# cooked-tomato.net
KiCad netlist of a schematic drawn in EAGLE
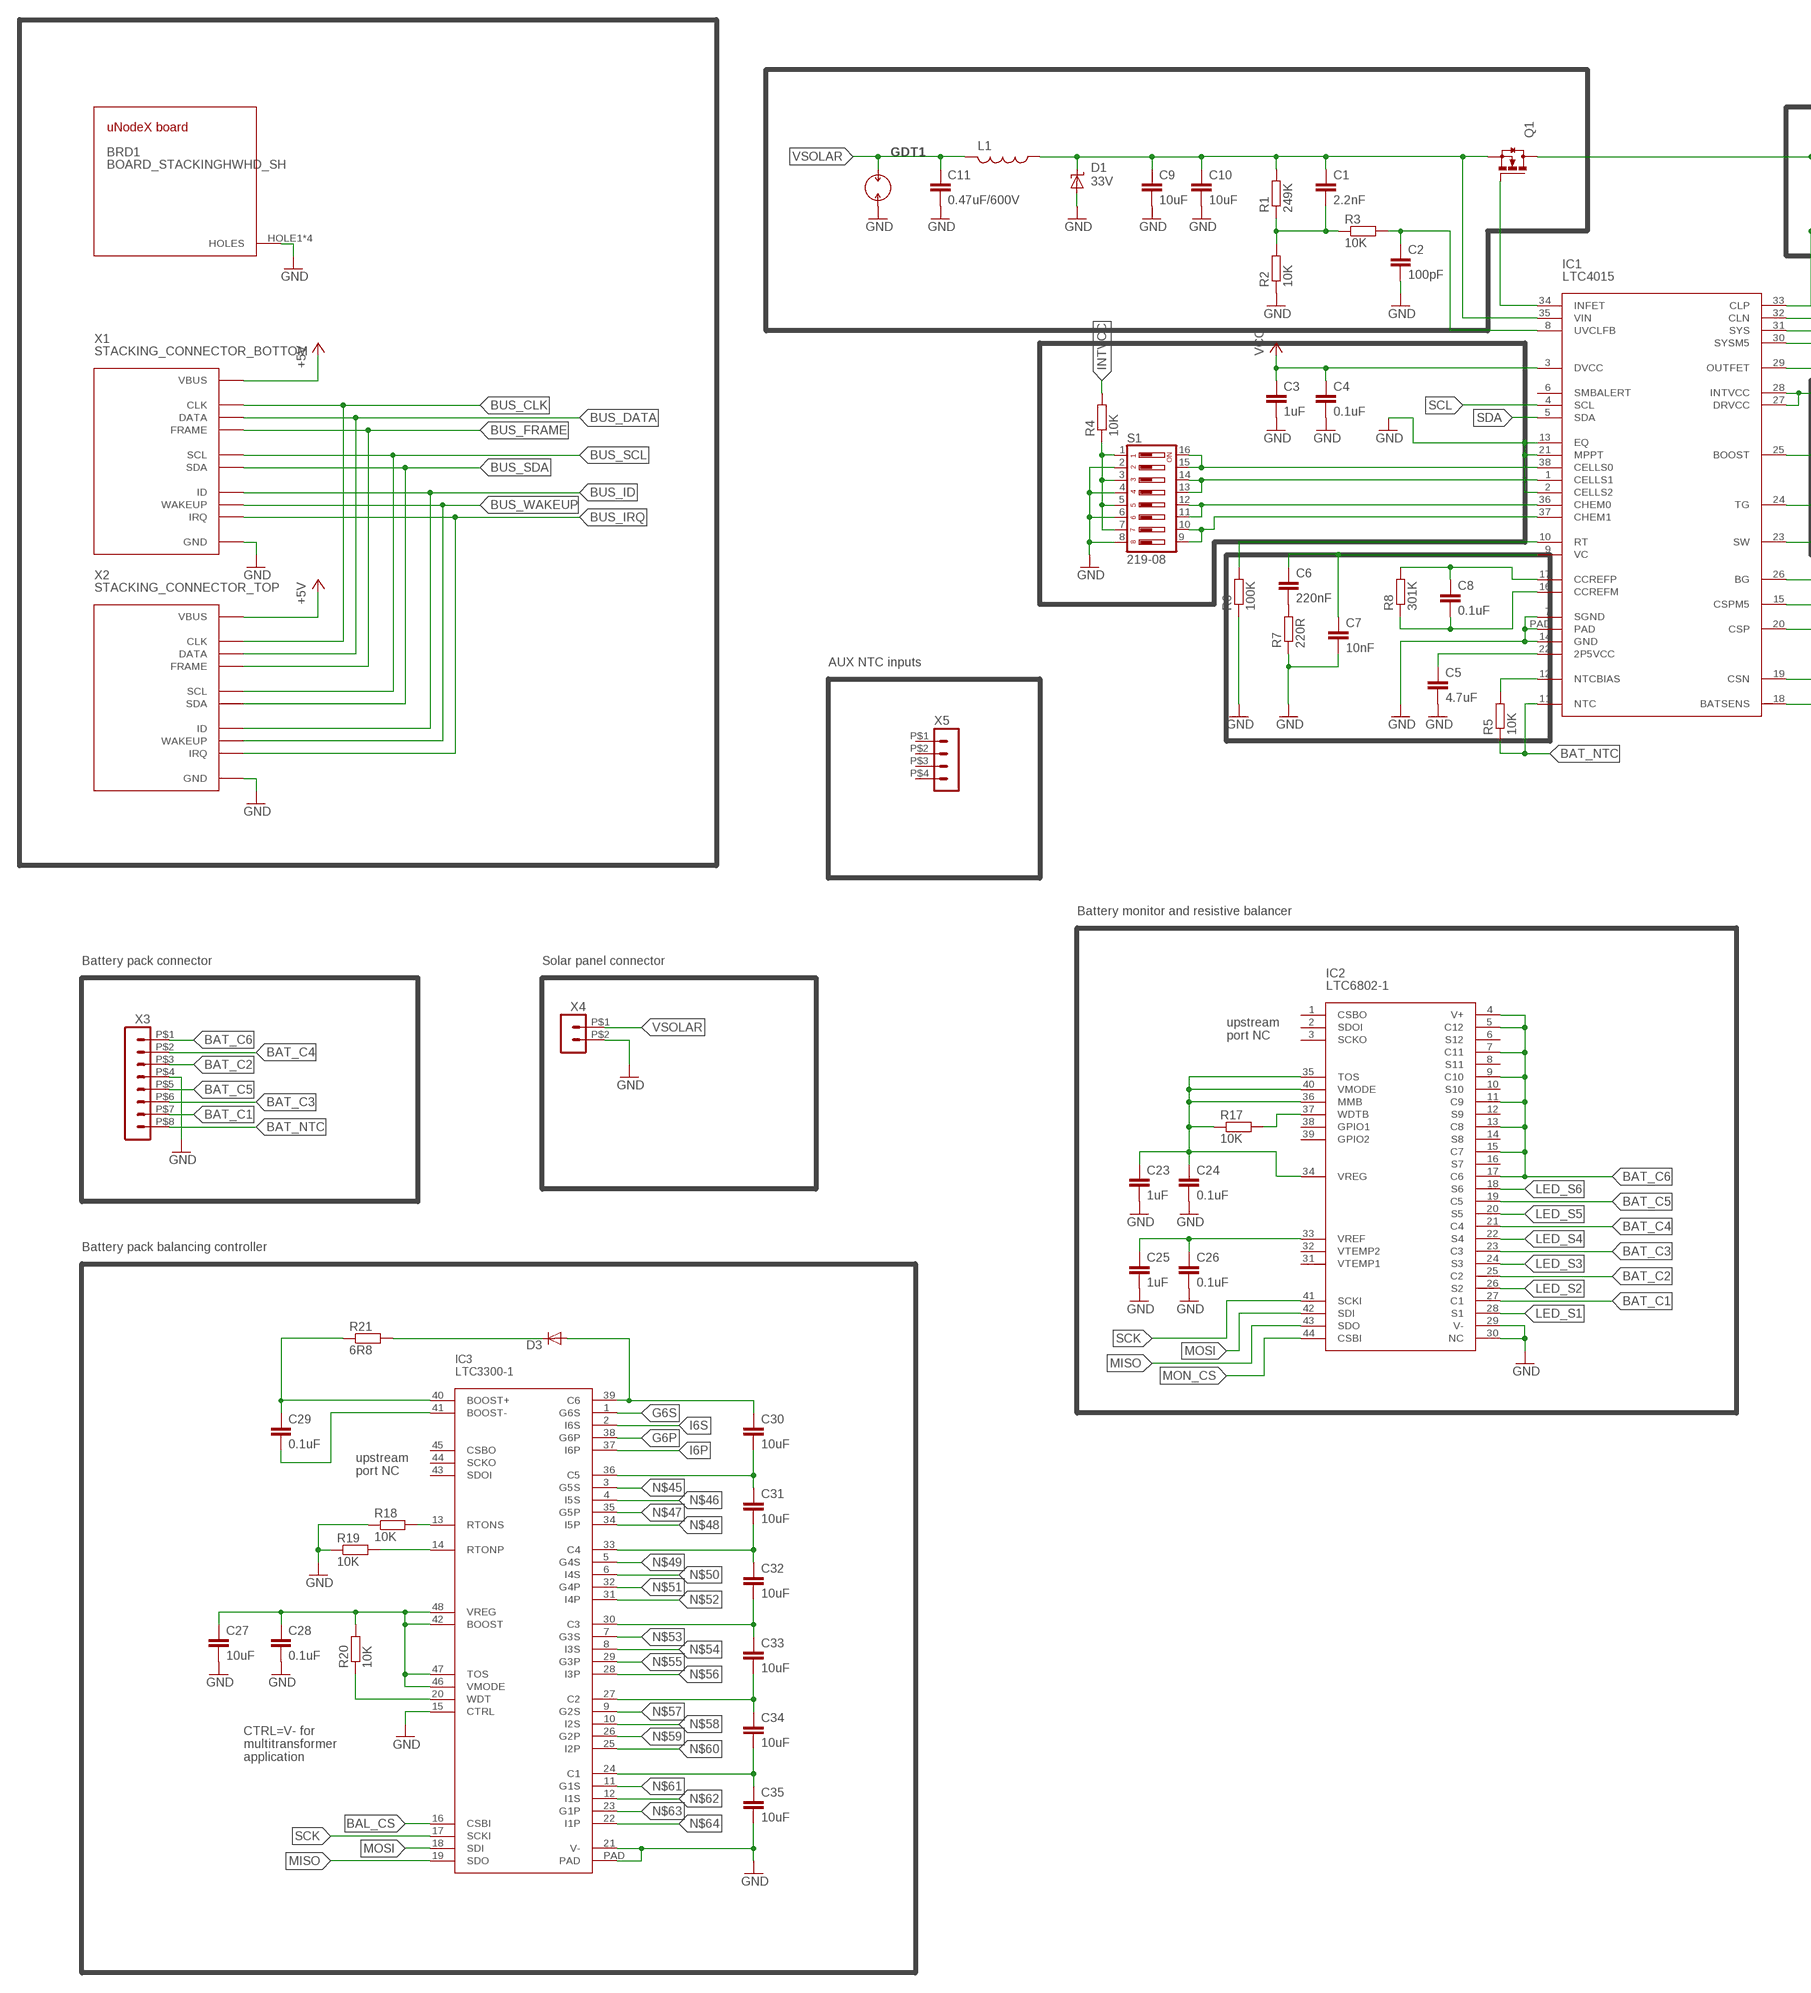
[diagram p0: schematic, sheet 1, part 1 of 3]
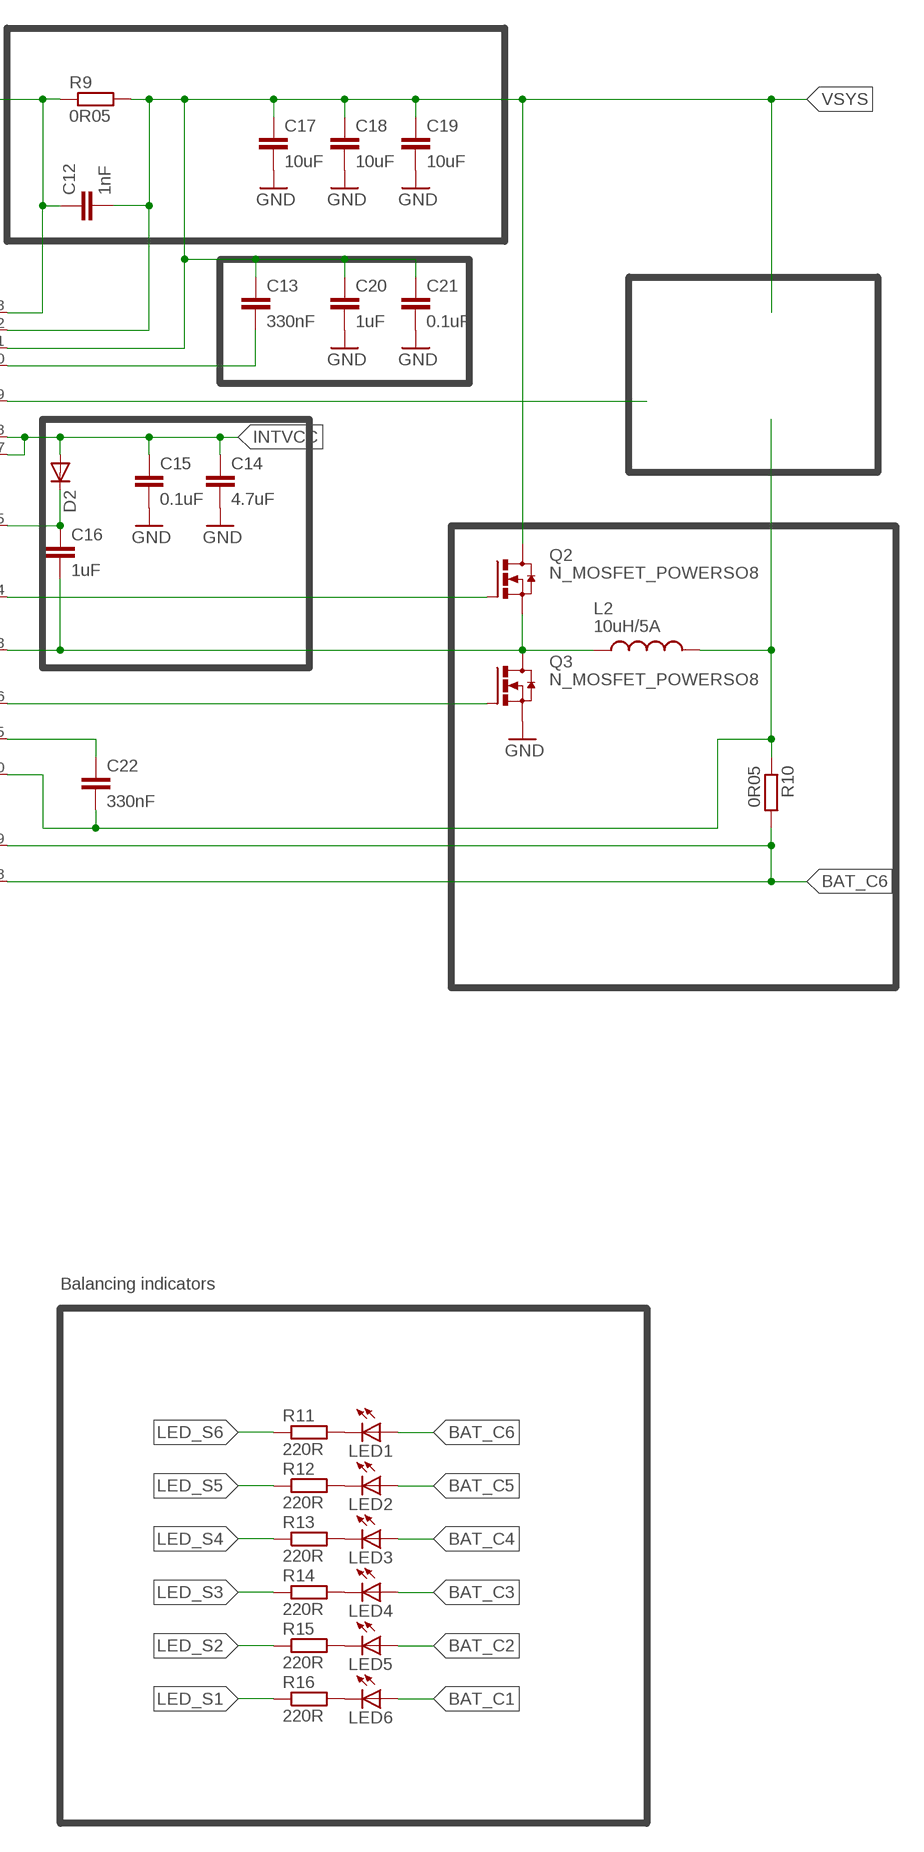
[diagram p1: schematic, sheet 1, part 2 of 3]
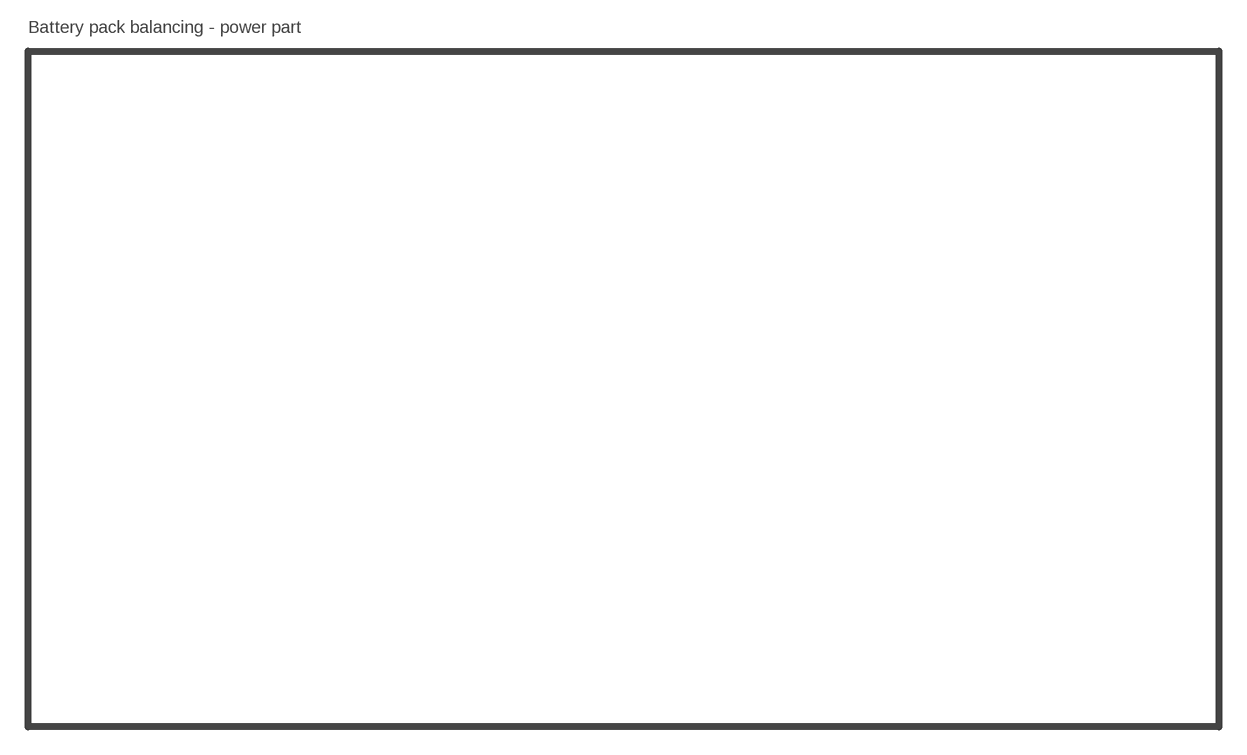
[diagram p2: schematic, sheet 1, part 3 of 3]

(export (version "E")
  (design (tool "Eeschema 10.0.6"))
  (components
    (comp (ref "BRD1")
      (value "BOARD_STACKINGHWHD_SH")
      (footprint "eagle-import:HWHD_SHARP_CORNERS")
      (libsource (lib "eagle-import") (part "BOARD_STACKINGHWHD_SH"))
    )
    (comp (ref "C1")
      (value "2.2nF")
      (footprint "eagle-import:C0603")
      (libsource (lib "eagle-import") (part "C-EUC0603"))
    )
    (comp (ref "C2")
      (value "100pF")
      (footprint "eagle-import:C0603")
      (libsource (lib "eagle-import") (part "C-EUC0603"))
    )
    (comp (ref "C3")
      (value "1uF")
      (footprint "eagle-import:C0603")
      (libsource (lib "eagle-import") (part "C-EUC0603"))
    )
    (comp (ref "C4")
      (value "0.1uF")
      (footprint "eagle-import:C0603")
      (libsource (lib "eagle-import") (part "C-EUC0603"))
    )
    (comp (ref "C5")
      (value "4.7uF")
      (footprint "eagle-import:C0805")
      (libsource (lib "eagle-import") (part "C-EUC0805"))
    )
    (comp (ref "C6")
      (value "220nF")
      (footprint "eagle-import:C0603")
      (libsource (lib "eagle-import") (part "C-EUC0603"))
    )
    (comp (ref "C7")
      (value "10nF")
      (footprint "eagle-import:C0603")
      (libsource (lib "eagle-import") (part "C-EUC0603"))
    )
    (comp (ref "C8")
      (value "0.1uF")
      (footprint "eagle-import:C0603")
      (libsource (lib "eagle-import") (part "C-EUC0603"))
    )
    (comp (ref "C9")
      (value "10uF")
      (footprint "eagle-import:C2220K")
      (libsource (lib "eagle-import") (part "C-EUC2220K"))
    )
    (comp (ref "C10")
      (value "10uF")
      (footprint "eagle-import:C2220K")
      (libsource (lib "eagle-import") (part "C-EUC2220K"))
    )
    (comp (ref "C11")
      (value "0.47uF/600V")
      (footprint "eagle-import:C1206")
      (libsource (lib "eagle-import") (part "C-EUC1206"))
    )
    (comp (ref "C12")
      (value "1nF")
      (footprint "eagle-import:C0603")
      (libsource (lib "eagle-import") (part "C-EUC0603"))
    )
    (comp (ref "C13")
      (value "330nF")
      (footprint "eagle-import:C0603")
      (libsource (lib "eagle-import") (part "C-EUC0603"))
    )
    (comp (ref "C14")
      (value "4.7uF")
      (footprint "eagle-import:C0805")
      (libsource (lib "eagle-import") (part "C-EUC0805"))
    )
    (comp (ref "C15")
      (value "0.1uF")
      (footprint "eagle-import:C0603")
      (libsource (lib "eagle-import") (part "C-EUC0603"))
    )
    (comp (ref "C16")
      (value "1uF")
      (footprint "eagle-import:C0603")
      (libsource (lib "eagle-import") (part "C-EUC0603"))
    )
    (comp (ref "C17")
      (value "10uF")
      (footprint "eagle-import:C2220K")
      (libsource (lib "eagle-import") (part "C-EUC2220K"))
    )
    (comp (ref "C18")
      (value "10uF")
      (footprint "eagle-import:C2220K")
      (libsource (lib "eagle-import") (part "C-EUC2220K"))
    )
    (comp (ref "C19")
      (value "10uF")
      (footprint "eagle-import:C2220K")
      (libsource (lib "eagle-import") (part "C-EUC2220K"))
    )
    (comp (ref "C20")
      (value "1uF")
      (footprint "eagle-import:C0805")
      (libsource (lib "eagle-import") (part "C-EUC0805"))
    )
    (comp (ref "C21")
      (value "0.1uF")
      (footprint "eagle-import:C0603")
      (libsource (lib "eagle-import") (part "C-EUC0603"))
    )
    (comp (ref "C22")
      (value "330nF")
      (footprint "eagle-import:C0603")
      (libsource (lib "eagle-import") (part "C-EUC0603"))
    )
    (comp (ref "C23")
      (value "1uF")
      (footprint "eagle-import:C0805")
      (libsource (lib "eagle-import") (part "C-EUC0805"))
    )
    (comp (ref "C24")
      (value "0.1uF")
      (footprint "eagle-import:C0603")
      (libsource (lib "eagle-import") (part "C-EUC0603"))
    )
    (comp (ref "C25")
      (value "1uF")
      (footprint "eagle-import:C0805")
      (libsource (lib "eagle-import") (part "C-EUC0805"))
    )
    (comp (ref "C26")
      (value "0.1uF")
      (footprint "eagle-import:C0603")
      (libsource (lib "eagle-import") (part "C-EUC0603"))
    )
    (comp (ref "C27")
      (value "10uF")
      (footprint "eagle-import:C0805")
      (libsource (lib "eagle-import") (part "C-EUC0805"))
    )
    (comp (ref "C28")
      (value "0.1uF")
      (footprint "eagle-import:C0603")
      (libsource (lib "eagle-import") (part "C-EUC0603"))
    )
    (comp (ref "C29")
      (value "0.1uF")
      (footprint "eagle-import:C0603")
      (libsource (lib "eagle-import") (part "C-EUC0603"))
    )
    (comp (ref "C30")
      (value "10uF")
      (footprint "eagle-import:C1206")
      (libsource (lib "eagle-import") (part "C-EUC1206"))
    )
    (comp (ref "C31")
      (value "10uF")
      (footprint "eagle-import:C1206")
      (libsource (lib "eagle-import") (part "C-EUC1206"))
    )
    (comp (ref "C32")
      (value "10uF")
      (footprint "eagle-import:C1206")
      (libsource (lib "eagle-import") (part "C-EUC1206"))
    )
    (comp (ref "C33")
      (value "10uF")
      (footprint "eagle-import:C1206")
      (libsource (lib "eagle-import") (part "C-EUC1206"))
    )
    (comp (ref "C34")
      (value "10uF")
      (footprint "eagle-import:C1206")
      (libsource (lib "eagle-import") (part "C-EUC1206"))
    )
    (comp (ref "C35")
      (value "10uF")
      (footprint "eagle-import:C1206")
      (libsource (lib "eagle-import") (part "C-EUC1206"))
    )
    (comp (ref "D1")
      (value "33V")
      (footprint "eagle-import:SMBJ")
      (libsource (lib "eagle-import") (part "SUPPRESSOR-SMBJ"))
    )
    (comp (ref "D2")
      (value "DIODE-SOD323-W")
      (footprint "eagle-import:SOD323-W")
      (libsource (lib "eagle-import") (part "DIODE-SOD323-W"))
    )
    (comp (ref "D3")
      (value "DIODE-SOD323-W")
      (footprint "eagle-import:SOD323-W")
      (libsource (lib "eagle-import") (part "DIODE-SOD323-W"))
    )
    (comp (ref "GDT1")
      (value "2035-09-SM-RPLF")
      (footprint "eagle-import:2035-09-SM-RPLF")
      (libsource (lib "eagle-import") (part "2035-09-SM-RPLF"))
    )
    (comp (ref "IC1")
      (value "LTC4015")
      (footprint "eagle-import:QFN38")
      (libsource (lib "eagle-import") (part "LTC4015"))
    )
    (comp (ref "IC2")
      (value "LTC6802-1")
      (footprint "eagle-import:SSOP44")
      (libsource (lib "eagle-import") (part "LTC6802-1"))
    )
    (comp (ref "IC3")
      (value "LTC3300-1")
      (footprint "eagle-import:LQFP48")
      (libsource (lib "eagle-import") (part "LTC3300-1"))
    )
    (comp (ref "L1")
      (value "L-USL4532P")
      (footprint "eagle-import:L4532P")
      (libsource (lib "eagle-import") (part "L-USL4532P"))
    )
    (comp (ref "L2")
      (value "10uH/5A")
      (footprint "eagle-import:L7070")
      (libsource (lib "eagle-import") (part "INDUCTOR7070"))
    )
    (comp (ref "LED1")
      (value "LEDCHIP-LED0805")
      (footprint "eagle-import:CHIP-LED0805")
      (libsource (lib "eagle-import") (part "LEDCHIP-LED0805"))
    )
    (comp (ref "LED2")
      (value "LEDCHIP-LED0805")
      (footprint "eagle-import:CHIP-LED0805")
      (libsource (lib "eagle-import") (part "LEDCHIP-LED0805"))
    )
    (comp (ref "LED3")
      (value "LEDCHIP-LED0805")
      (footprint "eagle-import:CHIP-LED0805")
      (libsource (lib "eagle-import") (part "LEDCHIP-LED0805"))
    )
    (comp (ref "LED4")
      (value "LEDCHIP-LED0805")
      (footprint "eagle-import:CHIP-LED0805")
      (libsource (lib "eagle-import") (part "LEDCHIP-LED0805"))
    )
    (comp (ref "LED5")
      (value "LEDCHIP-LED0805")
      (footprint "eagle-import:CHIP-LED0805")
      (libsource (lib "eagle-import") (part "LEDCHIP-LED0805"))
    )
    (comp (ref "LED6")
      (value "LEDCHIP-LED0805")
      (footprint "eagle-import:CHIP-LED0805")
      (libsource (lib "eagle-import") (part "LEDCHIP-LED0805"))
    )
    (comp (ref "Q1")
      (value "N_MOSFET_POWERSO8")
      (footprint "eagle-import:POWERSO8")
      (libsource (lib "eagle-import") (part "N_MOSFET_POWERSO8"))
    )
    (comp (ref "Q2")
      (value "N_MOSFET_POWERSO8")
      (footprint "eagle-import:POWERSO8")
      (libsource (lib "eagle-import") (part "N_MOSFET_POWERSO8"))
    )
    (comp (ref "Q3")
      (value "N_MOSFET_POWERSO8")
      (footprint "eagle-import:POWERSO8")
      (libsource (lib "eagle-import") (part "N_MOSFET_POWERSO8"))
    )
    (comp (ref "R1")
      (value "249K")
      (footprint "eagle-import:R0603")
      (libsource (lib "eagle-import") (part "R-EU_R0603"))
    )
    (comp (ref "R2")
      (value "10K")
      (footprint "eagle-import:R0603")
      (libsource (lib "eagle-import") (part "R-EU_R0603"))
    )
    (comp (ref "R3")
      (value "10K")
      (footprint "eagle-import:R0603")
      (libsource (lib "eagle-import") (part "R-EU_R0603"))
    )
    (comp (ref "R4")
      (value "10K")
      (footprint "eagle-import:R0603")
      (libsource (lib "eagle-import") (part "R-EU_R0603"))
    )
    (comp (ref "R5")
      (value "10K")
      (footprint "eagle-import:R0603")
      (libsource (lib "eagle-import") (part "R-EU_R0603"))
    )
    (comp (ref "R6")
      (value "100K")
      (footprint "eagle-import:R0603")
      (libsource (lib "eagle-import") (part "R-EU_R0603"))
    )
    (comp (ref "R7")
      (value "220R")
      (footprint "eagle-import:R0603")
      (libsource (lib "eagle-import") (part "R-EU_R0603"))
    )
    (comp (ref "R8")
      (value "301K")
      (footprint "eagle-import:R0603")
      (libsource (lib "eagle-import") (part "R-EU_R0603"))
    )
    (comp (ref "R9")
      (value "0R05")
      (footprint "eagle-import:R2512")
      (libsource (lib "eagle-import") (part "R-EU_R2512"))
    )
    (comp (ref "R10")
      (value "0R05")
      (footprint "eagle-import:R2512")
      (libsource (lib "eagle-import") (part "R-EU_R2512"))
    )
    (comp (ref "R11")
      (value "220R")
      (footprint "eagle-import:R0603")
      (libsource (lib "eagle-import") (part "R-EU_R0603"))
    )
    (comp (ref "R12")
      (value "220R")
      (footprint "eagle-import:R0603")
      (libsource (lib "eagle-import") (part "R-EU_R0603"))
    )
    (comp (ref "R13")
      (value "220R")
      (footprint "eagle-import:R0603")
      (libsource (lib "eagle-import") (part "R-EU_R0603"))
    )
    (comp (ref "R14")
      (value "220R")
      (footprint "eagle-import:R0603")
      (libsource (lib "eagle-import") (part "R-EU_R0603"))
    )
    (comp (ref "R15")
      (value "220R")
      (footprint "eagle-import:R0603")
      (libsource (lib "eagle-import") (part "R-EU_R0603"))
    )
    (comp (ref "R16")
      (value "220R")
      (footprint "eagle-import:R0603")
      (libsource (lib "eagle-import") (part "R-EU_R0603"))
    )
    (comp (ref "R17")
      (value "10K")
      (footprint "eagle-import:R0603")
      (libsource (lib "eagle-import") (part "R-EU_R0603"))
    )
    (comp (ref "R18")
      (value "10K")
      (footprint "eagle-import:R0603")
      (libsource (lib "eagle-import") (part "R-EU_R0603"))
    )
    (comp (ref "R19")
      (value "10K")
      (footprint "eagle-import:R0603")
      (libsource (lib "eagle-import") (part "R-EU_R0603"))
    )
    (comp (ref "R20")
      (value "10K")
      (footprint "eagle-import:R0603")
      (libsource (lib "eagle-import") (part "R-EU_R0603"))
    )
    (comp (ref "R21")
      (value "6R8")
      (footprint "eagle-import:R0603")
      (libsource (lib "eagle-import") (part "R-EU_R0603"))
    )
    (comp (ref "S1")
      (value "219-08")
      (footprint "eagle-import:CTS-219-08")
      (libsource (lib "eagle-import") (part "219-08"))
    )
    (comp (ref "X1")
      (value "STACKING_CONNECTOR_BOTTOM")
      (footprint "eagle-import:HAR-FLEX-BOTTOM-12P")
      (libsource (lib "eagle-import") (part "STACKING_CONNECTOR_BOTTOM"))
    )
    (comp (ref "X2")
      (value "STACKING_CONNECTOR_TOP")
      (footprint "eagle-import:HAR-FLEX-TOP-12P")
      (libsource (lib "eagle-import") (part "STACKING_CONNECTOR_TOP"))
    )
    (comp (ref "X3")
      (value "HEADER_POS8_43045-0800")
      (footprint "eagle-import:43045-0800")
      (libsource (lib "eagle-import") (part "HEADER_POS8_?43045-0800"))
    )
    (comp (ref "X4")
      (value "HEADER_POS2_43650-0200")
      (footprint "eagle-import:43650-0200")
      (libsource (lib "eagle-import") (part "HEADER_POS2_?43650-0200"))
    )
    (comp (ref "X5")
      (value "HEADER_POS4_43045-0401")
      (footprint "eagle-import:43045-0400")
      (libsource (lib "eagle-import") (part "HEADER_POS4_?43045-0401"))
    )
  )
  (nets
    (net (code "1") (name "+5V") (class "Default")
      (node (ref "X1") (pin "VBUS") (pinfunction "VBUS_VBUS") (pintype "bidirectional"))
      (node (ref "X2") (pin "VBUS") (pinfunction "VBUS_VBUS") (pintype "bidirectional"))
    )
    (net (code "2") (name "BAL_CS") (class "Default")
      (node (ref "IC3") (pin "16") (pinfunction "CSBI_16") (pintype "bidirectional"))
    )
    (net (code "3") (name "BAT_C1") (class "Default")
      (node (ref "IC2") (pin "27") (pinfunction "C1_27") (pintype "bidirectional"))
      (node (ref "LED6") (pin "A") (pinfunction "A_A") (pintype "passive"))
      (node (ref "X3") (pin "P$7") (pinfunction "7_P$7") (pintype "passive"))
    )
    (net (code "4") (name "BAT_C2") (class "Default")
      (node (ref "IC2") (pin "25") (pinfunction "C2_25") (pintype "bidirectional"))
      (node (ref "LED5") (pin "A") (pinfunction "A_A") (pintype "passive"))
      (node (ref "X3") (pin "P$3") (pinfunction "3_P$3") (pintype "passive"))
    )
    (net (code "5") (name "BAT_C3") (class "Default")
      (node (ref "IC2") (pin "23") (pinfunction "C3_23") (pintype "bidirectional"))
      (node (ref "LED4") (pin "A") (pinfunction "A_A") (pintype "passive"))
      (node (ref "X3") (pin "P$6") (pinfunction "6_P$6") (pintype "passive"))
    )
    (net (code "6") (name "BAT_C4") (class "Default")
      (node (ref "IC2") (pin "21") (pinfunction "C4_21") (pintype "bidirectional"))
      (node (ref "LED3") (pin "A") (pinfunction "A_A") (pintype "passive"))
      (node (ref "X3") (pin "P$2") (pinfunction "2_P$2") (pintype "passive"))
    )
    (net (code "7") (name "BAT_C5") (class "Default")
      (node (ref "IC2") (pin "19") (pinfunction "C5_19") (pintype "bidirectional"))
      (node (ref "LED2") (pin "A") (pinfunction "A_A") (pintype "passive"))
      (node (ref "X3") (pin "P$5") (pinfunction "5_P$5") (pintype "passive"))
    )
    (net (code "8") (name "BAT_C6") (class "Default")
      (node (ref "IC1") (pin "18") (pinfunction "BATSENS_18") (pintype "bidirectional"))
      (node (ref "IC1") (pin "19") (pinfunction "CSN_19") (pintype "bidirectional"))
      (node (ref "IC2") (pin "11") (pinfunction "C9_11") (pintype "bidirectional"))
      (node (ref "IC2") (pin "13") (pinfunction "C8_13") (pintype "bidirectional"))
      (node (ref "IC2") (pin "15") (pinfunction "C7_15") (pintype "bidirectional"))
      (node (ref "IC2") (pin "17") (pinfunction "C6_17") (pintype "bidirectional"))
      (node (ref "IC2") (pin "4") (pinfunction "V+_4") (pintype "bidirectional"))
      (node (ref "IC2") (pin "5") (pinfunction "C12_5") (pintype "bidirectional"))
      (node (ref "IC2") (pin "7") (pinfunction "C11_7") (pintype "bidirectional"))
      (node (ref "IC2") (pin "9") (pinfunction "C10_9") (pintype "bidirectional"))
      (node (ref "LED1") (pin "A") (pinfunction "A_A") (pintype "passive"))
      (node (ref "R10") (pin "2") (pinfunction "2_2") (pintype "passive"))
      (node (ref "X3") (pin "P$1") (pinfunction "1_P$1") (pintype "passive"))
    )
    (net (code "9") (name "BAT_NTC") (class "Default")
      (node (ref "IC1") (pin "11") (pinfunction "NTC_11") (pintype "bidirectional"))
      (node (ref "R5") (pin "1") (pinfunction "1_1") (pintype "passive"))
      (node (ref "X3") (pin "P$8") (pinfunction "8_P$8") (pintype "passive"))
    )
    (net (code "10") (name "BUS_CLK") (class "Default")
      (node (ref "X1") (pin "CLK") (pinfunction "CLK_CLK") (pintype "bidirectional"))
      (node (ref "X2") (pin "CLK") (pinfunction "CLK_CLK") (pintype "bidirectional"))
    )
    (net (code "11") (name "BUS_DATA") (class "Default")
      (node (ref "X1") (pin "DATA") (pinfunction "DATA_DATA") (pintype "bidirectional"))
      (node (ref "X2") (pin "DATA") (pinfunction "DATA_DATA") (pintype "bidirectional"))
    )
    (net (code "12") (name "BUS_FRAME") (class "Default")
      (node (ref "X1") (pin "FRAME") (pinfunction "FRAME_FRAME") (pintype "bidirectional"))
      (node (ref "X2") (pin "FRAME") (pinfunction "FRAME_FRAME") (pintype "bidirectional"))
    )
    (net (code "13") (name "BUS_ID") (class "Default")
      (node (ref "X1") (pin "ID") (pinfunction "ID_ID") (pintype "bidirectional"))
      (node (ref "X2") (pin "ID") (pinfunction "ID_ID") (pintype "bidirectional"))
    )
    (net (code "14") (name "BUS_IRQ") (class "Default")
      (node (ref "X1") (pin "IRQ") (pinfunction "IRQ_IRQ") (pintype "bidirectional"))
      (node (ref "X2") (pin "IRQ") (pinfunction "IRQ_IRQ") (pintype "bidirectional"))
    )
    (net (code "15") (name "BUS_SCL") (class "Default")
      (node (ref "X1") (pin "SCL") (pinfunction "SCL_SCL") (pintype "bidirectional"))
      (node (ref "X2") (pin "SCL") (pinfunction "SCL_SCL") (pintype "bidirectional"))
    )
    (net (code "16") (name "BUS_SDA") (class "Default")
      (node (ref "X1") (pin "SDA") (pinfunction "SDA_SDA") (pintype "bidirectional"))
      (node (ref "X2") (pin "SDA") (pinfunction "SDA_SDA") (pintype "bidirectional"))
    )
    (net (code "17") (name "BUS_WAKEUP") (class "Default")
      (node (ref "X1") (pin "WAKEUP") (pinfunction "WAKEUP_WAKEUP") (pintype "bidirectional"))
      (node (ref "X2") (pin "WAKEUP") (pinfunction "WAKEUP_WAKEUP") (pintype "bidirectional"))
    )
    (net (code "18") (name "G6P") (class "Default")
      (node (ref "IC3") (pin "38") (pinfunction "G6P_38") (pintype "bidirectional"))
    )
    (net (code "19") (name "G6S") (class "Default")
      (node (ref "IC3") (pin "1") (pinfunction "G6S_1") (pintype "bidirectional"))
    )
    (net (code "20") (name "GND") (class "Default")
      (node (ref "BRD1") (pin "HOLE1") (pinfunction "HOLES_HOLE1") (pintype "bidirectional"))
      (node (ref "BRD1") (pin "HOLE2") (pinfunction "HOLES_HOLE2") (pintype "bidirectional"))
      (node (ref "BRD1") (pin "HOLE3") (pinfunction "HOLES_HOLE3") (pintype "bidirectional"))
      (node (ref "BRD1") (pin "HOLE4") (pinfunction "HOLES_HOLE4") (pintype "bidirectional"))
      (node (ref "C10") (pin "2") (pinfunction "2_2") (pintype "passive"))
      (node (ref "C11") (pin "2") (pinfunction "2_2") (pintype "passive"))
      (node (ref "C14") (pin "2") (pinfunction "2_2") (pintype "passive"))
      (node (ref "C15") (pin "2") (pinfunction "2_2") (pintype "passive"))
      (node (ref "C17") (pin "2") (pinfunction "2_2") (pintype "passive"))
      (node (ref "C18") (pin "2") (pinfunction "2_2") (pintype "passive"))
      (node (ref "C19") (pin "2") (pinfunction "2_2") (pintype "passive"))
      (node (ref "C2") (pin "2") (pinfunction "2_2") (pintype "passive"))
      (node (ref "C20") (pin "2") (pinfunction "2_2") (pintype "passive"))
      (node (ref "C21") (pin "2") (pinfunction "2_2") (pintype "passive"))
      (node (ref "C23") (pin "2") (pinfunction "2_2") (pintype "passive"))
      (node (ref "C24") (pin "2") (pinfunction "2_2") (pintype "passive"))
      (node (ref "C25") (pin "2") (pinfunction "2_2") (pintype "passive"))
      (node (ref "C26") (pin "2") (pinfunction "2_2") (pintype "passive"))
      (node (ref "C27") (pin "2") (pinfunction "2_2") (pintype "passive"))
      (node (ref "C28") (pin "2") (pinfunction "2_2") (pintype "passive"))
      (node (ref "C3") (pin "2") (pinfunction "2_2") (pintype "passive"))
      (node (ref "C35") (pin "2") (pinfunction "2_2") (pintype "passive"))
      (node (ref "C4") (pin "2") (pinfunction "2_2") (pintype "passive"))
      (node (ref "C5") (pin "2") (pinfunction "2_2") (pintype "passive"))
      (node (ref "C7") (pin "2") (pinfunction "2_2") (pintype "passive"))
      (node (ref "C9") (pin "2") (pinfunction "2_2") (pintype "passive"))
      (node (ref "D1") (pin "A") (pinfunction "A_A") (pintype "passive"))
      (node (ref "GDT1") (pin "2") (pinfunction "2_2") (pintype "bidirectional"))
      (node (ref "IC1") (pin "13") (pinfunction "EQ_13") (pintype "bidirectional"))
      (node (ref "IC1") (pin "14") (pinfunction "GND_14") (pintype "bidirectional"))
      (node (ref "IC1") (pin "2") (pinfunction "CELLS2_2") (pintype "bidirectional"))
      (node (ref "IC1") (pin "21") (pinfunction "MPPT_21") (pintype "bidirectional"))
      (node (ref "IC1") (pin "7") (pinfunction "SGND_7") (pintype "bidirectional"))
      (node (ref "IC1") (pin "PAD") (pinfunction "PAD_PAD") (pintype "bidirectional"))
      (node (ref "IC2") (pin "29") (pinfunction "V-_29") (pintype "bidirectional"))
      (node (ref "IC2") (pin "30") (pinfunction "NC_30") (pintype "bidirectional"))
      (node (ref "IC3") (pin "15") (pinfunction "CTRL_15") (pintype "bidirectional"))
      (node (ref "IC3") (pin "21") (pinfunction "V-_21") (pintype "bidirectional"))
      (node (ref "IC3") (pin "PAD") (pinfunction "PAD_PAD") (pintype "bidirectional"))
      (node (ref "Q3") (pin "1") (pinfunction "S_1") (pintype "passive"))
      (node (ref "Q3") (pin "2") (pinfunction "S_2") (pintype "passive"))
      (node (ref "Q3") (pin "3") (pinfunction "S_3") (pintype "passive"))
      (node (ref "R18") (pin "1") (pinfunction "1_1") (pintype "passive"))
      (node (ref "R19") (pin "1") (pinfunction "1_1") (pintype "passive"))
      (node (ref "R2") (pin "1") (pinfunction "1_1") (pintype "passive"))
      (node (ref "R6") (pin "1") (pinfunction "1_1") (pintype "passive"))
      (node (ref "R7") (pin "1") (pinfunction "1_1") (pintype "passive"))
      (node (ref "S1") (pin "2") (pinfunction "2_2") (pintype "passive"))
      (node (ref "S1") (pin "4") (pinfunction "4_4") (pintype "passive"))
      (node (ref "S1") (pin "6") (pinfunction "6_6") (pintype "passive"))
      (node (ref "S1") (pin "8") (pinfunction "8_8") (pintype "passive"))
      (node (ref "X1") (pin "GND1") (pinfunction "GND_GND1") (pintype "bidirectional"))
      (node (ref "X1") (pin "GND2") (pinfunction "GND_GND2") (pintype "bidirectional"))
      (node (ref "X1") (pin "GND3") (pinfunction "GND_GND3") (pintype "bidirectional"))
      (node (ref "X1") (pin "H1") (pinfunction "GND_H1") (pintype "bidirectional"))
      (node (ref "X1") (pin "H2") (pinfunction "GND_H2") (pintype "bidirectional"))
      (node (ref "X1") (pin "H3") (pinfunction "GND_H3") (pintype "bidirectional"))
      (node (ref "X1") (pin "H4") (pinfunction "GND_H4") (pintype "bidirectional"))
      (node (ref "X2") (pin "GND1") (pinfunction "GND_GND1") (pintype "bidirectional"))
      (node (ref "X2") (pin "GND2") (pinfunction "GND_GND2") (pintype "bidirectional"))
      (node (ref "X2") (pin "GND3") (pinfunction "GND_GND3") (pintype "bidirectional"))
      (node (ref "X2") (pin "H1") (pinfunction "GND_H1") (pintype "bidirectional"))
      (node (ref "X2") (pin "H2") (pinfunction "GND_H2") (pintype "bidirectional"))
      (node (ref "X2") (pin "H3") (pinfunction "GND_H3") (pintype "bidirectional"))
      (node (ref "X2") (pin "H4") (pinfunction "GND_H4") (pintype "bidirectional"))
      (node (ref "X3") (pin "P$4") (pinfunction "4_P$4") (pintype "passive"))
      (node (ref "X4") (pin "P$2") (pinfunction "2_P$2") (pintype "passive"))
    )
    (net (code "21") (name "I6P") (class "Default")
      (node (ref "IC3") (pin "37") (pinfunction "I6P_37") (pintype "bidirectional"))
    )
    (net (code "22") (name "I6S") (class "Default")
      (node (ref "IC3") (pin "2") (pinfunction "I6S_2") (pintype "bidirectional"))
    )
    (net (code "23") (name "INTVCC") (class "Default")
      (node (ref "C14") (pin "1") (pinfunction "1_1") (pintype "passive"))
      (node (ref "C15") (pin "1") (pinfunction "1_1") (pintype "passive"))
      (node (ref "D2") (pin "A") (pinfunction "A_A") (pintype "passive"))
      (node (ref "IC1") (pin "27") (pinfunction "DRVCC_27") (pintype "bidirectional"))
      (node (ref "IC1") (pin "28") (pinfunction "INTVCC_28") (pintype "bidirectional"))
      (node (ref "R4") (pin "2") (pinfunction "2_2") (pintype "passive"))
    )
    (net (code "24") (name "LED_S1") (class "Default")
      (node (ref "IC2") (pin "28") (pinfunction "S1_28") (pintype "bidirectional"))
      (node (ref "R16") (pin "1") (pinfunction "1_1") (pintype "passive"))
    )
    (net (code "25") (name "LED_S2") (class "Default")
      (node (ref "IC2") (pin "26") (pinfunction "S2_26") (pintype "bidirectional"))
      (node (ref "R15") (pin "1") (pinfunction "1_1") (pintype "passive"))
    )
    (net (code "26") (name "LED_S3") (class "Default")
      (node (ref "IC2") (pin "24") (pinfunction "S3_24") (pintype "bidirectional"))
      (node (ref "R14") (pin "1") (pinfunction "1_1") (pintype "passive"))
    )
    (net (code "27") (name "LED_S4") (class "Default")
      (node (ref "IC2") (pin "22") (pinfunction "S4_22") (pintype "bidirectional"))
      (node (ref "R13") (pin "1") (pinfunction "1_1") (pintype "passive"))
    )
    (net (code "28") (name "LED_S5") (class "Default")
      (node (ref "IC2") (pin "20") (pinfunction "S5_20") (pintype "bidirectional"))
      (node (ref "R12") (pin "1") (pinfunction "1_1") (pintype "passive"))
    )
    (net (code "29") (name "LED_S6") (class "Default")
      (node (ref "IC2") (pin "18") (pinfunction "S6_18") (pintype "bidirectional"))
      (node (ref "R11") (pin "1") (pinfunction "1_1") (pintype "passive"))
    )
    (net (code "30") (name "MISO") (class "Default")
      (node (ref "IC2") (pin "43") (pinfunction "SDO_43") (pintype "bidirectional"))
      (node (ref "IC3") (pin "19") (pinfunction "SDO_19") (pintype "bidirectional"))
    )
    (net (code "31") (name "MON_CS") (class "Default")
      (node (ref "IC2") (pin "44") (pinfunction "CSBI_44") (pintype "bidirectional"))
    )
    (net (code "32") (name "MOSI") (class "Default")
      (node (ref "IC2") (pin "42") (pinfunction "SDI_42") (pintype "bidirectional"))
      (node (ref "IC3") (pin "18") (pinfunction "SDI_18") (pintype "bidirectional"))
    )
    (net (code "33") (name "N$45") (class "Default")
      (node (ref "IC3") (pin "3") (pinfunction "G5S_3") (pintype "bidirectional"))
    )
    (net (code "34") (name "N$46") (class "Default")
      (node (ref "IC3") (pin "4") (pinfunction "I5S_4") (pintype "bidirectional"))
    )
    (net (code "35") (name "N$47") (class "Default")
      (node (ref "IC3") (pin "35") (pinfunction "G5P_35") (pintype "bidirectional"))
    )
    (net (code "36") (name "N$48") (class "Default")
      (node (ref "IC3") (pin "34") (pinfunction "I5P_34") (pintype "bidirectional"))
    )
    (net (code "37") (name "N$49") (class "Default")
      (node (ref "IC3") (pin "5") (pinfunction "G4S_5") (pintype "bidirectional"))
    )
    (net (code "38") (name "N$50") (class "Default")
      (node (ref "IC3") (pin "6") (pinfunction "I4S_6") (pintype "bidirectional"))
    )
    (net (code "39") (name "N$51") (class "Default")
      (node (ref "IC3") (pin "32") (pinfunction "G4P_32") (pintype "bidirectional"))
    )
    (net (code "40") (name "N$52") (class "Default")
      (node (ref "IC3") (pin "31") (pinfunction "I4P_31") (pintype "bidirectional"))
    )
    (net (code "41") (name "N$53") (class "Default")
      (node (ref "IC3") (pin "7") (pinfunction "G3S_7") (pintype "bidirectional"))
    )
    (net (code "42") (name "N$54") (class "Default")
      (node (ref "IC3") (pin "8") (pinfunction "I3S_8") (pintype "bidirectional"))
    )
    (net (code "43") (name "N$55") (class "Default")
      (node (ref "IC3") (pin "29") (pinfunction "G3P_29") (pintype "bidirectional"))
    )
    (net (code "44") (name "N$56") (class "Default")
      (node (ref "IC3") (pin "28") (pinfunction "I3P_28") (pintype "bidirectional"))
    )
    (net (code "45") (name "N$57") (class "Default")
      (node (ref "IC3") (pin "9") (pinfunction "G2S_9") (pintype "bidirectional"))
    )
    (net (code "46") (name "N$58") (class "Default")
      (node (ref "IC3") (pin "10") (pinfunction "I2S_10") (pintype "bidirectional"))
    )
    (net (code "47") (name "N$59") (class "Default")
      (node (ref "IC3") (pin "26") (pinfunction "G2P_26") (pintype "bidirectional"))
    )
    (net (code "48") (name "N$60") (class "Default")
      (node (ref "IC3") (pin "25") (pinfunction "I2P_25") (pintype "bidirectional"))
    )
    (net (code "49") (name "N$61") (class "Default")
      (node (ref "IC3") (pin "11") (pinfunction "G1S_11") (pintype "bidirectional"))
    )
    (net (code "50") (name "N$62") (class "Default")
      (node (ref "IC3") (pin "12") (pinfunction "I1S_12") (pintype "bidirectional"))
    )
    (net (code "51") (name "N$63") (class "Default")
      (node (ref "IC3") (pin "23") (pinfunction "G1P_23") (pintype "bidirectional"))
    )
    (net (code "52") (name "N$64") (class "Default")
      (node (ref "IC3") (pin "22") (pinfunction "I1P_22") (pintype "bidirectional"))
    )
    (net (code "53") (name "Net-(C1-Pad2)") (class "Default")
      (node (ref "C1") (pin "2") (pinfunction "2_2") (pintype "passive"))
      (node (ref "R1") (pin "1") (pinfunction "1_1") (pintype "passive"))
      (node (ref "R2") (pin "2") (pinfunction "2_2") (pintype "passive"))
      (node (ref "R3") (pin "1") (pinfunction "1_1") (pintype "passive"))
    )
    (net (code "54") (name "Net-(C6-Pad2)") (class "Default")
      (node (ref "C6") (pin "2") (pinfunction "2_2") (pintype "passive"))
      (node (ref "R7") (pin "2") (pinfunction "2_2") (pintype "passive"))
    )
    (net (code "55") (name "Net-(D3-PadC)") (class "Default")
      (node (ref "D3") (pin "C") (pinfunction "C_C") (pintype "passive"))
      (node (ref "R21") (pin "2") (pinfunction "2_2") (pintype "passive"))
    )
    (net (code "56") (name "Net-(IC1-2P5VCC)") (class "Default")
      (node (ref "C5") (pin "1") (pinfunction "1_1") (pintype "passive"))
      (node (ref "IC1") (pin "22") (pinfunction "2P5VCC_22") (pintype "bidirectional"))
    )
    (net (code "57") (name "Net-(IC1-BG)") (class "Default")
      (node (ref "IC1") (pin "26") (pinfunction "BG_26") (pintype "bidirectional"))
      (node (ref "Q3") (pin "4") (pinfunction "G_4") (pintype "passive"))
    )
    (net (code "58") (name "Net-(IC1-BOOST)") (class "Default")
      (node (ref "C16") (pin "1") (pinfunction "1_1") (pintype "passive"))
      (node (ref "D2") (pin "C") (pinfunction "C_C") (pintype "passive"))
      (node (ref "IC1") (pin "25") (pinfunction "BOOST_25") (pintype "bidirectional"))
    )
    (net (code "59") (name "Net-(IC1-CCREFM)") (class "Default")
      (node (ref "C8") (pin "2") (pinfunction "2_2") (pintype "passive"))
      (node (ref "IC1") (pin "16") (pinfunction "CCREFM_16") (pintype "bidirectional"))
      (node (ref "R8") (pin "1") (pinfunction "1_1") (pintype "passive"))
    )
    (net (code "60") (name "Net-(IC1-CCREFP)") (class "Default")
      (node (ref "C8") (pin "1") (pinfunction "1_1") (pintype "passive"))
      (node (ref "IC1") (pin "17") (pinfunction "CCREFP_17") (pintype "bidirectional"))
      (node (ref "R8") (pin "2") (pinfunction "2_2") (pintype "passive"))
    )
    (net (code "61") (name "Net-(IC1-CELLS0)") (class "Default")
      (node (ref "IC1") (pin "38") (pinfunction "CELLS0_38") (pintype "bidirectional"))
      (node (ref "S1") (pin "15") (pinfunction "15_15") (pintype "passive"))
      (node (ref "S1") (pin "16") (pinfunction "16_16") (pintype "passive"))
    )
    (net (code "62") (name "Net-(IC1-CELLS1)") (class "Default")
      (node (ref "IC1") (pin "1") (pinfunction "CELLS1_1") (pintype "bidirectional"))
      (node (ref "S1") (pin "13") (pinfunction "13_13") (pintype "passive"))
      (node (ref "S1") (pin "14") (pinfunction "14_14") (pintype "passive"))
    )
    (net (code "63") (name "Net-(IC1-CHEM0)") (class "Default")
      (node (ref "IC1") (pin "36") (pinfunction "CHEM0_36") (pintype "bidirectional"))
      (node (ref "S1") (pin "11") (pinfunction "11_11") (pintype "passive"))
      (node (ref "S1") (pin "12") (pinfunction "12_12") (pintype "passive"))
    )
    (net (code "64") (name "Net-(IC1-CHEM1)") (class "Default")
      (node (ref "IC1") (pin "37") (pinfunction "CHEM1_37") (pintype "bidirectional"))
      (node (ref "S1") (pin "10") (pinfunction "10_10") (pintype "passive"))
      (node (ref "S1") (pin "9") (pinfunction "9_9") (pintype "passive"))
    )
    (net (code "65") (name "Net-(IC1-CLP)") (class "Default")
      (node (ref "C12") (pin "1") (pinfunction "1_1") (pintype "passive"))
      (node (ref "IC1") (pin "33") (pinfunction "CLP_33") (pintype "bidirectional"))
      (node (ref "Q1") (pin "5") (pinfunction "D_5") (pintype "passive"))
      (node (ref "Q1") (pin "6") (pinfunction "D_6") (pintype "passive"))
      (node (ref "Q1") (pin "7") (pinfunction "D_7") (pintype "passive"))
      (node (ref "Q1") (pin "8") (pinfunction "D_8") (pintype "passive"))
      (node (ref "Q1") (pin "PAD") (pinfunction "D_PAD") (pintype "passive"))
      (node (ref "R9") (pin "1") (pinfunction "1_1") (pintype "passive"))
    )
    (net (code "66") (name "Net-(IC1-CSP)") (class "Default")
      (node (ref "C22") (pin "2") (pinfunction "2_2") (pintype "passive"))
      (node (ref "IC1") (pin "20") (pinfunction "CSP_20") (pintype "bidirectional"))
      (node (ref "L2") (pin "2") (pinfunction "2_2") (pintype "passive"))
      (node (ref "R10") (pin "1") (pinfunction "1_1") (pintype "passive"))
    )
    (net (code "67") (name "Net-(IC1-CSPM5)") (class "Default")
      (node (ref "C22") (pin "1") (pinfunction "1_1") (pintype "passive"))
      (node (ref "IC1") (pin "15") (pinfunction "CSPM5_15") (pintype "bidirectional"))
    )
    (net (code "68") (name "Net-(IC1-INFET)") (class "Default")
      (node (ref "IC1") (pin "34") (pinfunction "INFET_34") (pintype "bidirectional"))
      (node (ref "Q1") (pin "4") (pinfunction "G_4") (pintype "passive"))
    )
    (net (code "69") (name "Net-(IC1-NTCBIAS)") (class "Default")
      (node (ref "IC1") (pin "12") (pinfunction "NTCBIAS_12") (pintype "bidirectional"))
      (node (ref "R5") (pin "2") (pinfunction "2_2") (pintype "passive"))
    )
    (net (code "70") (name "Net-(IC1-RT)") (class "Default")
      (node (ref "IC1") (pin "10") (pinfunction "RT_10") (pintype "bidirectional"))
      (node (ref "R6") (pin "2") (pinfunction "2_2") (pintype "passive"))
    )
    (net (code "71") (name "Net-(IC1-SW)") (class "Default")
      (node (ref "C16") (pin "2") (pinfunction "2_2") (pintype "passive"))
      (node (ref "IC1") (pin "23") (pinfunction "SW_23") (pintype "bidirectional"))
      (node (ref "L2") (pin "1") (pinfunction "1_1") (pintype "passive"))
      (node (ref "Q2") (pin "1") (pinfunction "S_1") (pintype "passive"))
      (node (ref "Q2") (pin "2") (pinfunction "S_2") (pintype "passive"))
      (node (ref "Q2") (pin "3") (pinfunction "S_3") (pintype "passive"))
      (node (ref "Q3") (pin "5") (pinfunction "D_5") (pintype "passive"))
      (node (ref "Q3") (pin "6") (pinfunction "D_6") (pintype "passive"))
      (node (ref "Q3") (pin "7") (pinfunction "D_7") (pintype "passive"))
      (node (ref "Q3") (pin "8") (pinfunction "D_8") (pintype "passive"))
      (node (ref "Q3") (pin "PAD") (pinfunction "D_PAD") (pintype "passive"))
    )
    (net (code "72") (name "Net-(IC1-SYSM5)") (class "Default")
      (node (ref "C13") (pin "2") (pinfunction "2_2") (pintype "passive"))
      (node (ref "IC1") (pin "30") (pinfunction "SYSM5_30") (pintype "bidirectional"))
    )
    (net (code "73") (name "Net-(IC1-TG)") (class "Default")
      (node (ref "IC1") (pin "24") (pinfunction "TG_24") (pintype "bidirectional"))
      (node (ref "Q2") (pin "4") (pinfunction "G_4") (pintype "passive"))
    )
    (net (code "74") (name "Net-(IC1-UVCLFB)") (class "Default")
      (node (ref "C2") (pin "1") (pinfunction "1_1") (pintype "passive"))
      (node (ref "IC1") (pin "8") (pinfunction "UVCLFB_8") (pintype "bidirectional"))
      (node (ref "R3") (pin "2") (pinfunction "2_2") (pintype "passive"))
    )
    (net (code "75") (name "Net-(IC1-VC)") (class "Default")
      (node (ref "C6") (pin "1") (pinfunction "1_1") (pintype "passive"))
      (node (ref "C7") (pin "1") (pinfunction "1_1") (pintype "passive"))
      (node (ref "IC1") (pin "9") (pinfunction "VC_9") (pintype "bidirectional"))
    )
    (net (code "76") (name "Net-(IC1-VIN)") (class "Default")
      (node (ref "C1") (pin "1") (pinfunction "1_1") (pintype "passive"))
      (node (ref "C10") (pin "1") (pinfunction "1_1") (pintype "passive"))
      (node (ref "C9") (pin "1") (pinfunction "1_1") (pintype "passive"))
      (node (ref "D1") (pin "C") (pinfunction "C_C") (pintype "passive"))
      (node (ref "IC1") (pin "35") (pinfunction "VIN_35") (pintype "bidirectional"))
      (node (ref "L1") (pin "1") (pinfunction "1_1") (pintype "passive"))
      (node (ref "Q1") (pin "1") (pinfunction "S_1") (pintype "passive"))
      (node (ref "Q1") (pin "2") (pinfunction "S_2") (pintype "passive"))
      (node (ref "Q1") (pin "3") (pinfunction "S_3") (pintype "passive"))
      (node (ref "R1") (pin "2") (pinfunction "2_2") (pintype "passive"))
    )
    (net (code "77") (name "Net-(IC2-MMB)") (class "Default")
      (node (ref "C23") (pin "1") (pinfunction "1_1") (pintype "passive"))
      (node (ref "C24") (pin "1") (pinfunction "1_1") (pintype "passive"))
      (node (ref "IC2") (pin "34") (pinfunction "VREG_34") (pintype "bidirectional"))
      (node (ref "IC2") (pin "35") (pinfunction "TOS_35") (pintype "bidirectional"))
      (node (ref "IC2") (pin "36") (pinfunction "MMB_36") (pintype "bidirectional"))
      (node (ref "IC2") (pin "40") (pinfunction "VMODE_40") (pintype "bidirectional"))
      (node (ref "R17") (pin "1") (pinfunction "1_1") (pintype "passive"))
    )
    (net (code "78") (name "Net-(IC2-VREF)") (class "Default")
      (node (ref "C25") (pin "1") (pinfunction "1_1") (pintype "passive"))
      (node (ref "C26") (pin "1") (pinfunction "1_1") (pintype "passive"))
      (node (ref "IC2") (pin "33") (pinfunction "VREF_33") (pintype "bidirectional"))
    )
    (net (code "79") (name "Net-(IC2-WDTB)") (class "Default")
      (node (ref "IC2") (pin "37") (pinfunction "WDTB_37") (pintype "bidirectional"))
      (node (ref "R17") (pin "2") (pinfunction "2_2") (pintype "passive"))
    )
    (net (code "80") (name "Net-(IC3-BOOST)") (class "Default")
      (node (ref "C27") (pin "1") (pinfunction "1_1") (pintype "passive"))
      (node (ref "C28") (pin "1") (pinfunction "1_1") (pintype "passive"))
      (node (ref "IC3") (pin "42") (pinfunction "BOOST_42") (pintype "bidirectional"))
      (node (ref "IC3") (pin "46") (pinfunction "VMODE_46") (pintype "bidirectional"))
      (node (ref "IC3") (pin "47") (pinfunction "TOS_47") (pintype "bidirectional"))
      (node (ref "IC3") (pin "48") (pinfunction "VREG_48") (pintype "bidirectional"))
      (node (ref "R20") (pin "2") (pinfunction "2_2") (pintype "passive"))
    )
    (net (code "81") (name "Net-(IC3-BOOST+)") (class "Default")
      (node (ref "C29") (pin "1") (pinfunction "1_1") (pintype "passive"))
      (node (ref "IC3") (pin "40") (pinfunction "BOOST+_40") (pintype "bidirectional"))
      (node (ref "R21") (pin "1") (pinfunction "1_1") (pintype "passive"))
    )
    (net (code "82") (name "Net-(IC3-BOOST-)") (class "Default")
      (node (ref "C29") (pin "2") (pinfunction "2_2") (pintype "passive"))
      (node (ref "IC3") (pin "41") (pinfunction "BOOST-_41") (pintype "bidirectional"))
    )
    (net (code "83") (name "Net-(IC3-C1)") (class "Default")
      (node (ref "C34") (pin "2") (pinfunction "2_2") (pintype "passive"))
      (node (ref "C35") (pin "1") (pinfunction "1_1") (pintype "passive"))
      (node (ref "IC3") (pin "24") (pinfunction "C1_24") (pintype "bidirectional"))
    )
    (net (code "84") (name "Net-(IC3-C2)") (class "Default")
      (node (ref "C33") (pin "2") (pinfunction "2_2") (pintype "passive"))
      (node (ref "C34") (pin "1") (pinfunction "1_1") (pintype "passive"))
      (node (ref "IC3") (pin "27") (pinfunction "C2_27") (pintype "bidirectional"))
    )
    (net (code "85") (name "Net-(IC3-C3)") (class "Default")
      (node (ref "C32") (pin "2") (pinfunction "2_2") (pintype "passive"))
      (node (ref "C33") (pin "1") (pinfunction "1_1") (pintype "passive"))
      (node (ref "IC3") (pin "30") (pinfunction "C3_30") (pintype "bidirectional"))
    )
    (net (code "86") (name "Net-(IC3-C4)") (class "Default")
      (node (ref "C31") (pin "2") (pinfunction "2_2") (pintype "passive"))
      (node (ref "C32") (pin "1") (pinfunction "1_1") (pintype "passive"))
      (node (ref "IC3") (pin "33") (pinfunction "C4_33") (pintype "bidirectional"))
    )
    (net (code "87") (name "Net-(IC3-C5)") (class "Default")
      (node (ref "C30") (pin "2") (pinfunction "2_2") (pintype "passive"))
      (node (ref "C31") (pin "1") (pinfunction "1_1") (pintype "passive"))
      (node (ref "IC3") (pin "36") (pinfunction "C5_36") (pintype "bidirectional"))
    )
    (net (code "88") (name "Net-(IC3-C6)") (class "Default")
      (node (ref "C30") (pin "1") (pinfunction "1_1") (pintype "passive"))
      (node (ref "D3") (pin "A") (pinfunction "A_A") (pintype "passive"))
      (node (ref "IC3") (pin "39") (pinfunction "C6_39") (pintype "bidirectional"))
    )
    (net (code "89") (name "Net-(IC3-RTONP)") (class "Default")
      (node (ref "IC3") (pin "14") (pinfunction "RTONP_14") (pintype "bidirectional"))
      (node (ref "R19") (pin "2") (pinfunction "2_2") (pintype "passive"))
    )
    (net (code "90") (name "Net-(IC3-RTONS)") (class "Default")
      (node (ref "IC3") (pin "13") (pinfunction "RTONS_13") (pintype "bidirectional"))
      (node (ref "R18") (pin "2") (pinfunction "2_2") (pintype "passive"))
    )
    (net (code "91") (name "Net-(IC3-WDT)") (class "Default")
      (node (ref "IC3") (pin "20") (pinfunction "WDT_20") (pintype "bidirectional"))
      (node (ref "R20") (pin "1") (pinfunction "1_1") (pintype "passive"))
    )
    (net (code "92") (name "Net-(LED1-PadC)") (class "Default")
      (node (ref "LED1") (pin "C") (pinfunction "C_C") (pintype "passive"))
      (node (ref "R11") (pin "2") (pinfunction "2_2") (pintype "passive"))
    )
    (net (code "93") (name "Net-(LED2-PadC)") (class "Default")
      (node (ref "LED2") (pin "C") (pinfunction "C_C") (pintype "passive"))
      (node (ref "R12") (pin "2") (pinfunction "2_2") (pintype "passive"))
    )
    (net (code "94") (name "Net-(LED3-PadC)") (class "Default")
      (node (ref "LED3") (pin "C") (pinfunction "C_C") (pintype "passive"))
      (node (ref "R13") (pin "2") (pinfunction "2_2") (pintype "passive"))
    )
    (net (code "95") (name "Net-(LED4-PadC)") (class "Default")
      (node (ref "LED4") (pin "C") (pinfunction "C_C") (pintype "passive"))
      (node (ref "R14") (pin "2") (pinfunction "2_2") (pintype "passive"))
    )
    (net (code "96") (name "Net-(LED5-PadC)") (class "Default")
      (node (ref "LED5") (pin "C") (pinfunction "C_C") (pintype "passive"))
      (node (ref "R15") (pin "2") (pinfunction "2_2") (pintype "passive"))
    )
    (net (code "97") (name "Net-(LED6-PadC)") (class "Default")
      (node (ref "LED6") (pin "C") (pinfunction "C_C") (pintype "passive"))
      (node (ref "R16") (pin "2") (pinfunction "2_2") (pintype "passive"))
    )
    (net (code "98") (name "Net-(R4-Pad1)") (class "Default")
      (node (ref "R4") (pin "1") (pinfunction "1_1") (pintype "passive"))
      (node (ref "S1") (pin "1") (pinfunction "1_1") (pintype "passive"))
      (node (ref "S1") (pin "3") (pinfunction "3_3") (pintype "passive"))
      (node (ref "S1") (pin "5") (pinfunction "5_5") (pintype "passive"))
      (node (ref "S1") (pin "7") (pinfunction "7_7") (pintype "passive"))
    )
    (net (code "99") (name "SCK") (class "Default")
      (node (ref "IC2") (pin "41") (pinfunction "SCKI_41") (pintype "bidirectional"))
      (node (ref "IC3") (pin "17") (pinfunction "SCKI_17") (pintype "bidirectional"))
    )
    (net (code "100") (name "SCL") (class "Default")
      (node (ref "IC1") (pin "4") (pinfunction "SCL_4") (pintype "bidirectional"))
    )
    (net (code "101") (name "SDA") (class "Default")
      (node (ref "IC1") (pin "5") (pinfunction "SDA_5") (pintype "bidirectional"))
    )
    (net (code "102") (name "VCC") (class "Default")
      (node (ref "C3") (pin "1") (pinfunction "1_1") (pintype "passive"))
      (node (ref "C4") (pin "1") (pinfunction "1_1") (pintype "passive"))
      (node (ref "IC1") (pin "3") (pinfunction "DVCC_3") (pintype "bidirectional"))
    )
    (net (code "103") (name "VSOLAR") (class "Default")
      (node (ref "C11") (pin "1") (pinfunction "1_1") (pintype "passive"))
      (node (ref "GDT1") (pin "1") (pinfunction "1_1") (pintype "bidirectional"))
      (node (ref "L1") (pin "2") (pinfunction "2_2") (pintype "passive"))
      (node (ref "X4") (pin "P$1") (pinfunction "1_P$1") (pintype "passive"))
    )
    (net (code "104") (name "VSYS") (class "Default")
      (node (ref "C12") (pin "2") (pinfunction "2_2") (pintype "passive"))
      (node (ref "C13") (pin "1") (pinfunction "1_1") (pintype "passive"))
      (node (ref "C17") (pin "1") (pinfunction "1_1") (pintype "passive"))
      (node (ref "C18") (pin "1") (pinfunction "1_1") (pintype "passive"))
      (node (ref "C19") (pin "1") (pinfunction "1_1") (pintype "passive"))
      (node (ref "C20") (pin "1") (pinfunction "1_1") (pintype "passive"))
      (node (ref "C21") (pin "1") (pinfunction "1_1") (pintype "passive"))
      (node (ref "IC1") (pin "31") (pinfunction "SYS_31") (pintype "bidirectional"))
      (node (ref "IC1") (pin "32") (pinfunction "CLN_32") (pintype "bidirectional"))
      (node (ref "Q2") (pin "5") (pinfunction "D_5") (pintype "passive"))
      (node (ref "Q2") (pin "6") (pinfunction "D_6") (pintype "passive"))
      (node (ref "Q2") (pin "7") (pinfunction "D_7") (pintype "passive"))
      (node (ref "Q2") (pin "8") (pinfunction "D_8") (pintype "passive"))
      (node (ref "Q2") (pin "PAD") (pinfunction "D_PAD") (pintype "passive"))
      (node (ref "R9") (pin "2") (pinfunction "2_2") (pintype "passive"))
    )
    (net (code "105") (name "unconnected-(IC1-OUTFET-Pad29)") (class "Default")
      (node (ref "IC1") (pin "29") (pinfunction "OUTFET_29") (pintype "bidirectional"))
    )
    (net (code "106") (name "unconnected-(IC1-SMBALERT-Pad6)") (class "Default")
      (node (ref "IC1") (pin "6") (pinfunction "SMBALERT_6") (pintype "bidirectional"))
    )
    (net (code "107") (name "unconnected-(IC2-CSBO-Pad1)") (class "Default")
      (node (ref "IC2") (pin "1") (pinfunction "CSBO_1") (pintype "bidirectional"))
    )
    (net (code "108") (name "unconnected-(IC2-GPIO1-Pad38)") (class "Default")
      (node (ref "IC2") (pin "38") (pinfunction "GPIO1_38") (pintype "bidirectional"))
    )
    (net (code "109") (name "unconnected-(IC2-GPIO2-Pad39)") (class "Default")
      (node (ref "IC2") (pin "39") (pinfunction "GPIO2_39") (pintype "bidirectional"))
    )
    (net (code "110") (name "unconnected-(IC2-S7-Pad16)") (class "Default")
      (node (ref "IC2") (pin "16") (pinfunction "S7_16") (pintype "bidirectional"))
    )
    (net (code "111") (name "unconnected-(IC2-S8-Pad14)") (class "Default")
      (node (ref "IC2") (pin "14") (pinfunction "S8_14") (pintype "bidirectional"))
    )
    (net (code "112") (name "unconnected-(IC2-S9-Pad12)") (class "Default")
      (node (ref "IC2") (pin "12") (pinfunction "S9_12") (pintype "bidirectional"))
    )
    (net (code "113") (name "unconnected-(IC2-S10-Pad10)") (class "Default")
      (node (ref "IC2") (pin "10") (pinfunction "S10_10") (pintype "bidirectional"))
    )
    (net (code "114") (name "unconnected-(IC2-S11-Pad8)") (class "Default")
      (node (ref "IC2") (pin "8") (pinfunction "S11_8") (pintype "bidirectional"))
    )
    (net (code "115") (name "unconnected-(IC2-S12-Pad6)") (class "Default")
      (node (ref "IC2") (pin "6") (pinfunction "S12_6") (pintype "bidirectional"))
    )
    (net (code "116") (name "unconnected-(IC2-SCKO-Pad3)") (class "Default")
      (node (ref "IC2") (pin "3") (pinfunction "SCKO_3") (pintype "bidirectional"))
    )
    (net (code "117") (name "unconnected-(IC2-SDOI-Pad2)") (class "Default")
      (node (ref "IC2") (pin "2") (pinfunction "SDOI_2") (pintype "bidirectional"))
    )
    (net (code "118") (name "unconnected-(IC2-VTEMP1-Pad31)") (class "Default")
      (node (ref "IC2") (pin "31") (pinfunction "VTEMP1_31") (pintype "bidirectional"))
    )
    (net (code "119") (name "unconnected-(IC2-VTEMP2-Pad32)") (class "Default")
      (node (ref "IC2") (pin "32") (pinfunction "VTEMP2_32") (pintype "bidirectional"))
    )
    (net (code "120") (name "unconnected-(IC3-CSBO-Pad45)") (class "Default")
      (node (ref "IC3") (pin "45") (pinfunction "CSBO_45") (pintype "bidirectional"))
    )
    (net (code "121") (name "unconnected-(IC3-SCKO-Pad44)") (class "Default")
      (node (ref "IC3") (pin "44") (pinfunction "SCKO_44") (pintype "bidirectional"))
    )
    (net (code "122") (name "unconnected-(IC3-SDOI-Pad43)") (class "Default")
      (node (ref "IC3") (pin "43") (pinfunction "SDOI_43") (pintype "bidirectional"))
    )
    (net (code "123") (name "unconnected-(X5-1-PadP$1)") (class "Default")
      (node (ref "X5") (pin "P$1") (pinfunction "1_P$1") (pintype "passive"))
    )
    (net (code "124") (name "unconnected-(X5-2-PadP$2)") (class "Default")
      (node (ref "X5") (pin "P$2") (pinfunction "2_P$2") (pintype "passive"))
    )
    (net (code "125") (name "unconnected-(X5-3-PadP$3)") (class "Default")
      (node (ref "X5") (pin "P$3") (pinfunction "3_P$3") (pintype "passive"))
    )
    (net (code "126") (name "unconnected-(X5-4-PadP$4)") (class "Default")
      (node (ref "X5") (pin "P$4") (pinfunction "4_P$4") (pintype "passive"))
    )
  )
)
